# PDB.net
KiCad netlist of a schematic drawn in EAGLE
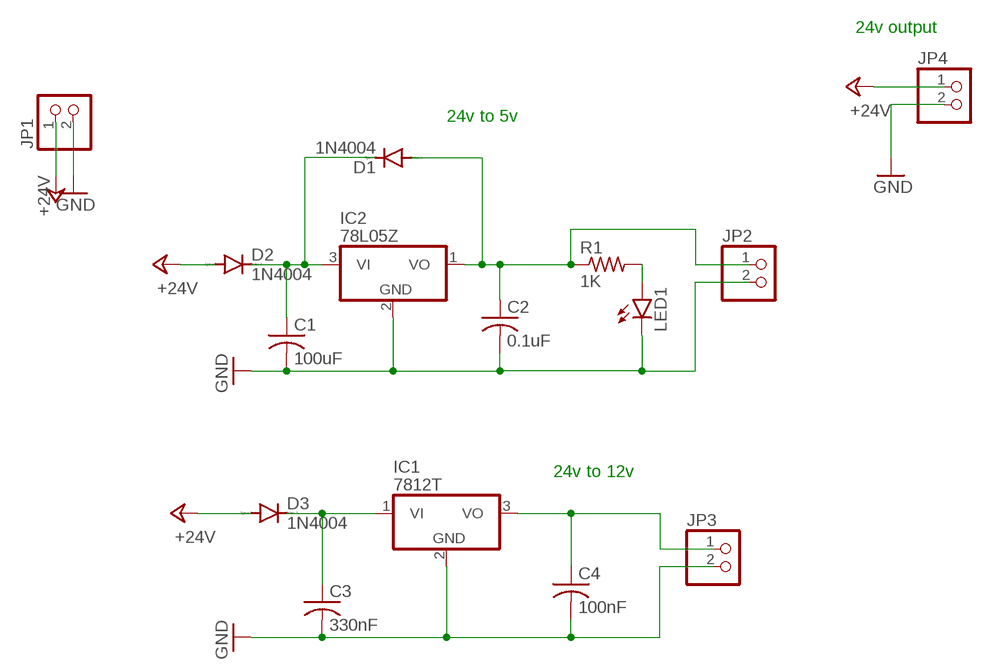
[diagram p0: schematic, sheet 1]

(export (version "E")
  (design (tool "Eeschema 10.0.6"))
  (components
    (comp (ref "C1")
      (value "100uF")
      (footprint "eagle-import:C025-024X044")
      (libsource (lib "eagle-import") (part "C-US025-024X044"))
    )
    (comp (ref "C2")
      (value "0.1uF")
      (footprint "eagle-import:C025-024X044")
      (libsource (lib "eagle-import") (part "C-US025-024X044"))
    )
    (comp (ref "C3")
      (value "330nF")
      (footprint "eagle-import:C025-024X044")
      (libsource (lib "eagle-import") (part "C-US025-024X044"))
    )
    (comp (ref "C4")
      (value "100nF")
      (footprint "eagle-import:C025-024X044")
      (libsource (lib "eagle-import") (part "C-US025-024X044"))
    )
    (comp (ref "D1")
      (value "1N4004")
      (footprint "eagle-import:DO41-10")
      (libsource (lib "eagle-import") (part "1N4004"))
    )
    (comp (ref "D2")
      (value "1N4004")
      (footprint "eagle-import:DO41-10")
      (libsource (lib "eagle-import") (part "1N4004"))
    )
    (comp (ref "D3")
      (value "1N4004")
      (footprint "eagle-import:DO41-10")
      (libsource (lib "eagle-import") (part "1N4004"))
    )
    (comp (ref "IC1")
      (value "7812T")
      (footprint "eagle-import:TO220H")
      (libsource (lib "eagle-import") (part "78T12"))
    )
    (comp (ref "IC2")
      (value "78L05Z")
      (footprint "eagle-import:TO92")
      (libsource (lib "eagle-import") (part "78ZL05"))
    )
    (comp (ref "JP1")
      (value "PINHD-1X2")
      (footprint "eagle-import:1X02")
      (libsource (lib "eagle-import") (part "PINHD-1X2"))
    )
    (comp (ref "JP2")
      (value "PINHD-1X2")
      (footprint "eagle-import:1X02")
      (libsource (lib "eagle-import") (part "PINHD-1X2"))
    )
    (comp (ref "JP3")
      (value "PINHD-1X2")
      (footprint "eagle-import:1X02")
      (libsource (lib "eagle-import") (part "PINHD-1X2"))
    )
    (comp (ref "JP4")
      (value "PINHD-1X2")
      (footprint "eagle-import:1X02")
      (libsource (lib "eagle-import") (part "PINHD-1X2"))
    )
    (comp (ref "LED1")
      (value "LED5MM")
      (footprint "eagle-import:LED5MM")
      (libsource (lib "eagle-import") (part "LED5MM"))
    )
    (comp (ref "R1")
      (value "1K")
      (footprint "eagle-import:0204_7")
      (libsource (lib "eagle-import") (part "R-US_0204/7"))
    )
  )
  (nets
    (net (code "1") (name "+24V") (class "Default")
      (node (ref "D2") (pin "A") (pinfunction "A_A") (pintype "passive"))
      (node (ref "D3") (pin "A") (pinfunction "A_A") (pintype "passive"))
      (node (ref "JP1") (pin "1") (pinfunction "1_1") (pintype "passive"))
      (node (ref "JP4") (pin "1") (pinfunction "1_1") (pintype "passive"))
    )
    (net (code "2") (name "GND") (class "Default")
      (node (ref "C1") (pin "2") (pinfunction "2_2") (pintype "passive"))
      (node (ref "C2") (pin "2") (pinfunction "2_2") (pintype "passive"))
      (node (ref "C3") (pin "2") (pinfunction "2_2") (pintype "passive"))
      (node (ref "C4") (pin "2") (pinfunction "2_2") (pintype "passive"))
      (node (ref "IC1") (pin "2") (pinfunction "GND_2") (pintype "passive"))
      (node (ref "IC2") (pin "2") (pinfunction "GND_2") (pintype "passive"))
      (node (ref "JP1") (pin "2") (pinfunction "2_2") (pintype "passive"))
      (node (ref "JP2") (pin "2") (pinfunction "2_2") (pintype "passive"))
      (node (ref "JP3") (pin "2") (pinfunction "2_2") (pintype "passive"))
      (node (ref "JP4") (pin "2") (pinfunction "2_2") (pintype "passive"))
      (node (ref "LED1") (pin "K") (pinfunction "C_K") (pintype "passive"))
    )
    (net (code "3") (name "Net-(IC1-VI)") (class "Default")
      (node (ref "C3") (pin "1") (pinfunction "1_1") (pintype "passive"))
      (node (ref "D3") (pin "C") (pinfunction "C_C") (pintype "passive"))
      (node (ref "IC1") (pin "1") (pinfunction "VI_1") (pintype "input"))
    )
    (net (code "4") (name "Net-(IC1-VO)") (class "Default")
      (node (ref "C4") (pin "1") (pinfunction "1_1") (pintype "passive"))
      (node (ref "IC1") (pin "3") (pinfunction "VO_3") (pintype "passive"))
      (node (ref "JP3") (pin "1") (pinfunction "1_1") (pintype "passive"))
    )
    (net (code "5") (name "Net-(IC2-VI)") (class "Default")
      (node (ref "C1") (pin "1") (pinfunction "1_1") (pintype "passive"))
      (node (ref "D1") (pin "C") (pinfunction "C_C") (pintype "passive"))
      (node (ref "D2") (pin "C") (pinfunction "C_C") (pintype "passive"))
      (node (ref "IC2") (pin "3") (pinfunction "VI_3") (pintype "input"))
    )
    (net (code "6") (name "Net-(IC2-VO)") (class "Default")
      (node (ref "C2") (pin "1") (pinfunction "1_1") (pintype "passive"))
      (node (ref "D1") (pin "A") (pinfunction "A_A") (pintype "passive"))
      (node (ref "IC2") (pin "1") (pinfunction "VO_1") (pintype "passive"))
      (node (ref "JP2") (pin "1") (pinfunction "1_1") (pintype "passive"))
      (node (ref "R1") (pin "1") (pinfunction "1_1") (pintype "passive"))
    )
    (net (code "7") (name "Net-(LED1-PadA)") (class "Default")
      (node (ref "LED1") (pin "A") (pinfunction "A_A") (pintype "passive"))
      (node (ref "R1") (pin "2") (pinfunction "2_2") (pintype "passive"))
    )
  )
)
